# Trace_Test.net
KiCad netlist of a schematic drawn in EAGLE
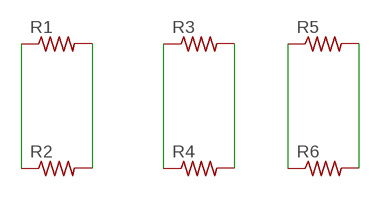
[diagram p0: schematic, sheet 1]

(export (version "E")
  (design (tool "Eeschema 10.0.6"))
  (components
    (comp (ref "R1")
      (value "R-US_0204/5")
      (footprint "eagle-import:0204_5")
      (libsource (lib "eagle-import") (part "R-US_0204/5"))
    )
    (comp (ref "R2")
      (value "R-US_0204/5")
      (footprint "eagle-import:0204_5")
      (libsource (lib "eagle-import") (part "R-US_0204/5"))
    )
    (comp (ref "R3")
      (value "R-US_0204/5")
      (footprint "eagle-import:0204_5")
      (libsource (lib "eagle-import") (part "R-US_0204/5"))
    )
    (comp (ref "R4")
      (value "R-US_0204/5")
      (footprint "eagle-import:0204_5")
      (libsource (lib "eagle-import") (part "R-US_0204/5"))
    )
    (comp (ref "R5")
      (value "R-US_0204/5")
      (footprint "eagle-import:0204_5")
      (libsource (lib "eagle-import") (part "R-US_0204/5"))
    )
    (comp (ref "R6")
      (value "R-US_0204/5")
      (footprint "eagle-import:0204_5")
      (libsource (lib "eagle-import") (part "R-US_0204/5"))
    )
  )
  (nets
    (net (code "1") (name "Net-(R1-Pad1)") (class "Default")
      (node (ref "R1") (pin "1") (pinfunction "1_1") (pintype "passive"))
      (node (ref "R2") (pin "1") (pinfunction "1_1") (pintype "passive"))
    )
    (net (code "2") (name "Net-(R1-Pad2)") (class "Default")
      (node (ref "R1") (pin "2") (pinfunction "2_2") (pintype "passive"))
      (node (ref "R2") (pin "2") (pinfunction "2_2") (pintype "passive"))
    )
    (net (code "3") (name "Net-(R3-Pad1)") (class "Default")
      (node (ref "R3") (pin "1") (pinfunction "1_1") (pintype "passive"))
      (node (ref "R4") (pin "1") (pinfunction "1_1") (pintype "passive"))
    )
    (net (code "4") (name "Net-(R3-Pad2)") (class "Default")
      (node (ref "R3") (pin "2") (pinfunction "2_2") (pintype "passive"))
      (node (ref "R4") (pin "2") (pinfunction "2_2") (pintype "passive"))
    )
    (net (code "5") (name "Net-(R5-Pad1)") (class "Default")
      (node (ref "R5") (pin "1") (pinfunction "1_1") (pintype "passive"))
      (node (ref "R6") (pin "1") (pinfunction "1_1") (pintype "passive"))
    )
    (net (code "6") (name "Net-(R5-Pad2)") (class "Default")
      (node (ref "R5") (pin "2") (pinfunction "2_2") (pintype "passive"))
      (node (ref "R6") (pin "2") (pinfunction "2_2") (pintype "passive"))
    )
  )
)
